# Remote_V2.net
KiCad netlist of a schematic drawn in Altium Designer
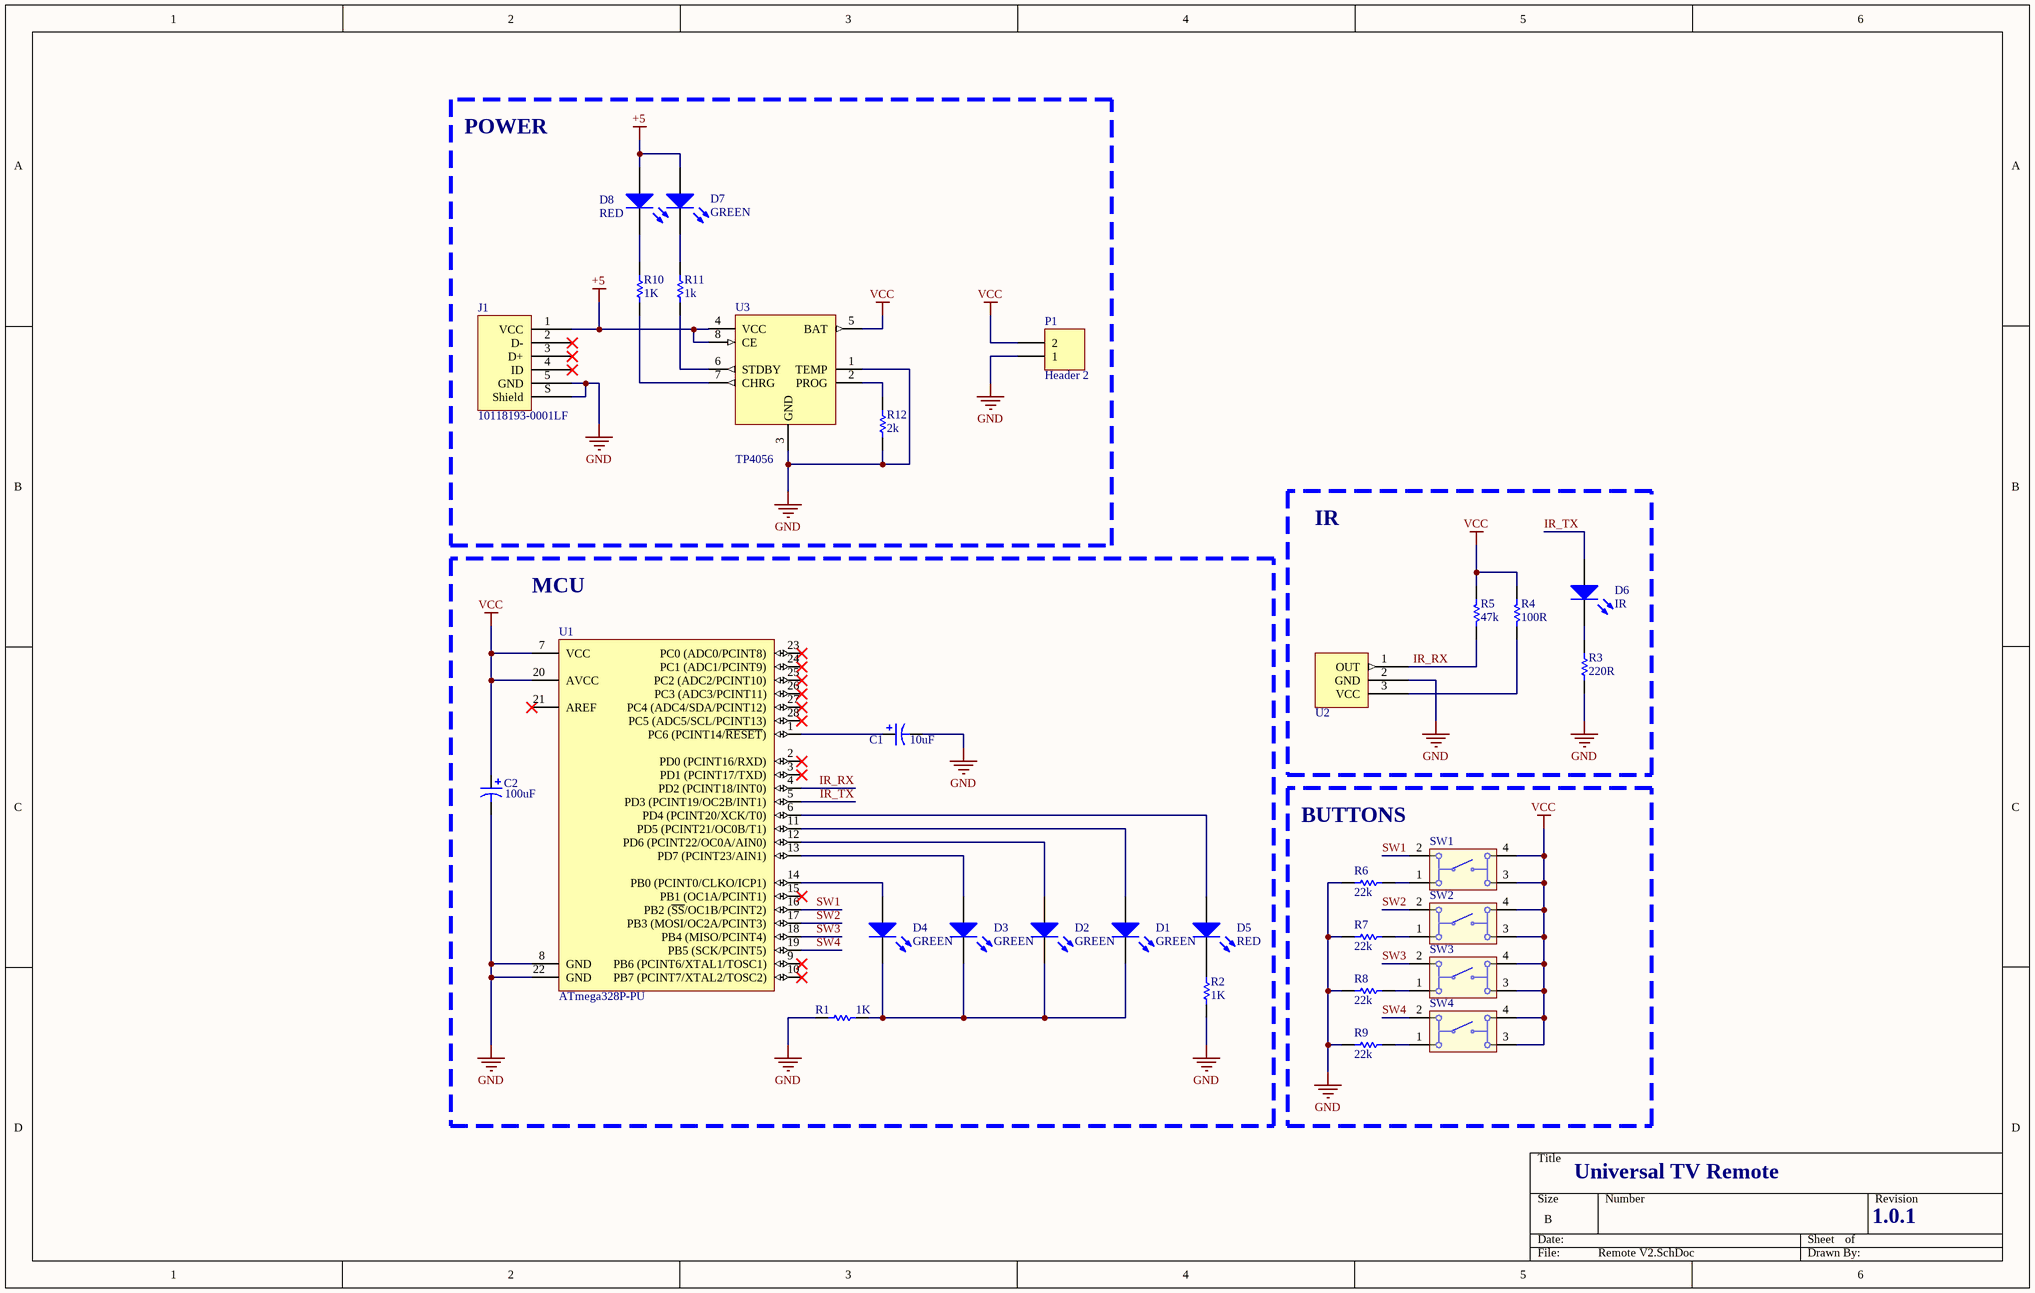
[diagram p0: Remote V2.SchDoc]

(export (version "E")
  (design (tool "Eeschema 10.0.6"))
  (components
    (comp (ref "C1")
      (value "10uF")
      (footprint "5mm CAP")
      (description "Polarized Capacitor (Radial)")
      (fields (field (name "Comment") "Cap Pol1") (field (name "PUBLISHER") "Altium Limited"))
      (libsource (lib "Miscellaneous Devices") (part "Cap Pol1"))
    )
    (comp (ref "C2")
      (value "100uF")
      (footprint "5mm CAP")
      (description "Polarized Capacitor (Radial)")
      (fields (field (name "Comment") "Cap Pol1") (field (name "PUBLISHER") "Altium Limited"))
      (libsource (lib "Miscellaneous Devices") (part "Cap Pol1"))
    )
    (comp (ref "D1")
      (value "GREEN")
      (footprint "5mm CAP")
      (description "Typical INFRARED GaAs LED")
      (fields (field (name "PUBLISHER") "Altium Limited"))
      (libsource (lib "Miscellaneous Devices") (part "LED0"))
    )
    (comp (ref "D2")
      (value "GREEN")
      (footprint "5mm CAP")
      (description "Typical INFRARED GaAs LED")
      (fields (field (name "PUBLISHER") "Altium Limited"))
      (libsource (lib "Miscellaneous Devices") (part "LED0"))
    )
    (comp (ref "D3")
      (value "GREEN")
      (footprint "5mm CAP")
      (description "Typical INFRARED GaAs LED")
      (fields (field (name "PUBLISHER") "Altium Limited"))
      (libsource (lib "Miscellaneous Devices") (part "LED0"))
    )
    (comp (ref "D4")
      (value "GREEN")
      (footprint "5mm CAP")
      (description "Typical INFRARED GaAs LED")
      (fields (field (name "PUBLISHER") "Altium Limited"))
      (libsource (lib "Miscellaneous Devices") (part "LED0"))
    )
    (comp (ref "D5")
      (value "RED")
      (footprint "5mm CAP")
      (description "Typical INFRARED GaAs LED")
      (fields (field (name "PUBLISHER") "Altium Limited"))
      (libsource (lib "Miscellaneous Devices") (part "LED0"))
    )
    (comp (ref "D6")
      (value "IR")
      (footprint "5mm CAP")
      (description "Typical INFRARED GaAs LED")
      (fields (field (name "PUBLISHER") "Altium Limited"))
      (libsource (lib "Miscellaneous Devices") (part "LED0"))
    )
    (comp (ref "D7")
      (value "GREEN")
      (footprint "5mm CAP")
      (description "Typical INFRARED GaAs LED")
      (fields (field (name "PUBLISHER") "Altium Limited"))
      (libsource (lib "Miscellaneous Devices") (part "LED0"))
    )
    (comp (ref "D8")
      (value "RED")
      (footprint "5mm CAP")
      (description "Typical INFRARED GaAs LED")
      (fields (field (name "PUBLISHER") "Altium Limited"))
      (libsource (lib "Miscellaneous Devices") (part "LED0"))
    )
    (comp (ref "J1")
      (value "10118193-0001LF")
      (footprint "FCI USB 10118193-0001LF")
      (description "CONN RCPT USB2.0 MICRO B SMD R/A")
      (fields (field (name "MANUFACTURER") "Amphenol ICC (FCI)"))
      (libsource (lib "Celestial Altium Library - altium_library(1)") (part "USB 2.0 Type B Micro"))
    )
    (comp (ref "P1")
      (value "Header 2")
      (footprint "HDR1X2")
      (description "Header, 2-Pin")
      (fields (field (name "PUBLISHER") "Altium Limited"))
      (libsource (lib "Miscellaneous Connectors") (part "Header 2"))
    )
    (comp (ref "R1")
      (value "1K")
      (footprint "AXIAL-0.3")
      (description "Resistor")
      (fields (field (name "Comment") "Res1") (field (name "PUBLISHER") "Altium Limited"))
      (libsource (lib "Miscellaneous Devices") (part "Res1"))
    )
    (comp (ref "R2")
      (value "1K")
      (footprint "AXIAL-0.3")
      (description "Resistor")
      (fields (field (name "Comment") "Res1") (field (name "PUBLISHER") "Altium Limited"))
      (libsource (lib "Miscellaneous Devices") (part "Res1"))
    )
    (comp (ref "R3")
      (value "220R")
      (footprint "AXIAL-0.3")
      (description "Resistor")
      (fields (field (name "Comment") "Res1") (field (name "PUBLISHER") "Altium Limited"))
      (libsource (lib "Miscellaneous Devices") (part "Res1"))
    )
    (comp (ref "R4")
      (value "100R")
      (footprint "AXIAL-0.3")
      (description "Resistor")
      (fields (field (name "Comment") "Res1") (field (name "PUBLISHER") "Altium Limited"))
      (libsource (lib "Miscellaneous Devices") (part "Res1"))
    )
    (comp (ref "R5")
      (value "47k")
      (footprint "AXIAL-0.3")
      (description "Resistor")
      (fields (field (name "Comment") "Res1") (field (name "PUBLISHER") "Altium Limited"))
      (libsource (lib "Miscellaneous Devices") (part "Res1"))
    )
    (comp (ref "R6")
      (value "22k")
      (footprint "AXIAL-0.3")
      (description "Resistor")
      (fields (field (name "Comment") "Res1") (field (name "PUBLISHER") "Altium Limited"))
      (libsource (lib "Miscellaneous Devices") (part "Res1"))
    )
    (comp (ref "R7")
      (value "22k")
      (footprint "AXIAL-0.3")
      (description "Resistor")
      (fields (field (name "Comment") "Res1") (field (name "PUBLISHER") "Altium Limited"))
      (libsource (lib "Miscellaneous Devices") (part "Res1"))
    )
    (comp (ref "R8")
      (value "22k")
      (footprint "AXIAL-0.3")
      (description "Resistor")
      (fields (field (name "Comment") "Res1") (field (name "PUBLISHER") "Altium Limited"))
      (libsource (lib "Miscellaneous Devices") (part "Res1"))
    )
    (comp (ref "R9")
      (value "22k")
      (footprint "AXIAL-0.3")
      (description "Resistor")
      (fields (field (name "Comment") "Res1") (field (name "PUBLISHER") "Altium Limited"))
      (libsource (lib "Miscellaneous Devices") (part "Res1"))
    )
    (comp (ref "R10")
      (value "1K")
      (footprint "6-0805_N")
      (description "Resistor")
      (fields (field (name "Comment") "Res1") (field (name "PUBLISHER") "Altium Limited"))
      (libsource (lib "Miscellaneous Devices") (part "Res1"))
    )
    (comp (ref "R11")
      (value "1k")
      (footprint "6-0805_N")
      (description "Resistor")
      (fields (field (name "Comment") "Res1") (field (name "PUBLISHER") "Altium Limited"))
      (libsource (lib "Miscellaneous Devices") (part "Res1"))
    )
    (comp (ref "R12")
      (value "2k")
      (footprint "6-0805_N")
      (description "Resistor")
      (fields (field (name "Comment") "Res1") (field (name "PUBLISHER") "Altium Limited"))
      (libsource (lib "Miscellaneous Devices") (part "Res1"))
    )
    (comp (ref "SW1")
      (value "430476085716")
      (footprint "SW_1825910-6-4")
      (description "WS-TATV THT Tact Switch 12X12 mm")
      (libsource (lib "WS-TATV THT Tact Switch 12X12 mm") (part "430476085716"))
    )
    (comp (ref "SW2")
      (value "430476085716")
      (footprint "SW_1825910-6-4")
      (description "WS-TATV THT Tact Switch 12X12 mm")
      (libsource (lib "WS-TATV THT Tact Switch 12X12 mm") (part "430476085716"))
    )
    (comp (ref "SW3")
      (value "430476085716")
      (footprint "SW_1825910-6-4")
      (description "WS-TATV THT Tact Switch 12X12 mm")
      (libsource (lib "WS-TATV THT Tact Switch 12X12 mm") (part "430476085716"))
    )
    (comp (ref "SW4")
      (value "430476085716")
      (footprint "SW_1825910-6-4")
      (description "WS-TATV THT Tact Switch 12X12 mm")
      (libsource (lib "WS-TATV THT Tact Switch 12X12 mm") (part "430476085716"))
    )
    (comp (ref "U1")
      (value "ATmega328P-PU")
      (footprint "28P3")
      (libsource (lib "Atmel Microcontroller megaAVR") (part "ATmega328P-PU"))
    )
    (comp (ref "U2")
      (value "CHO 1838")
      (footprint "TO-220-AB")
      (description "IR Receiver")
      (libsource (lib "Symobls") (part "CHO 1838"))
    )
    (comp (ref "U3") (value "TP4056") (footprint "Universal SOP 8") (libsource (lib "SMD") (part "TP4056")))
  )
  (nets
    (net (code "1") (name "+5") (class "Default")
      (node (ref "D7") (pin "1") (pinfunction "A_1") (pintype "passive"))
      (node (ref "D8") (pin "1") (pinfunction "A_1") (pintype "passive"))
      (node (ref "J1") (pin "1") (pinfunction "VCC_1") (pintype "passive"))
      (node (ref "U3") (pin "4") (pinfunction "VCC_4") (pintype "power_in"))
      (node (ref "U3") (pin "8") (pinfunction "CE_8") (pintype "input"))
    )
    (net (code "2") (name "/IR_RX") (class "Default")
      (node (ref "R5") (pin "1") (pinfunction "1_1") (pintype "passive"))
      (node (ref "U1") (pin "4") (pinfunction "PD2_(PCINT18/INT0)_4") (pintype "bidirectional"))
      (node (ref "U2") (pin "1") (pinfunction "OUT_1") (pintype "output"))
    )
    (net (code "3") (name "/IR_TX") (class "Default")
      (node (ref "D6") (pin "1") (pinfunction "A_1") (pintype "passive"))
      (node (ref "U1") (pin "5") (pinfunction "PD3_(PCINT19/OC2B/INT1)_5") (pintype "bidirectional"))
    )
    (net (code "4") (name "/SW1") (class "Default")
      (node (ref "SW1") (pin "2") (pinfunction "2_2") (pintype "passive"))
      (node (ref "U1") (pin "16") (pinfunction "PB2_(~{SS}/OC1B/PCINT2)_16") (pintype "bidirectional"))
    )
    (net (code "5") (name "/SW2") (class "Default")
      (node (ref "SW2") (pin "2") (pinfunction "2_2") (pintype "passive"))
      (node (ref "U1") (pin "17") (pinfunction "PB3_(MOSI/OC2A/PCINT3)_17") (pintype "bidirectional"))
    )
    (net (code "6") (name "/SW3") (class "Default")
      (node (ref "SW3") (pin "2") (pinfunction "2_2") (pintype "passive"))
      (node (ref "U1") (pin "18") (pinfunction "PB4_(MISO/PCINT4)_18") (pintype "bidirectional"))
    )
    (net (code "7") (name "/SW4") (class "Default")
      (node (ref "SW4") (pin "2") (pinfunction "2_2") (pintype "passive"))
      (node (ref "U1") (pin "19") (pinfunction "PB5_(SCK/PCINT5)_19") (pintype "bidirectional"))
    )
    (net (code "8") (name "GND") (class "Default")
      (node (ref "C1") (pin "2") (pinfunction "2_2") (pintype "passive"))
      (node (ref "C2") (pin "2") (pinfunction "2_2") (pintype "passive"))
      (node (ref "J1") (pin "5") (pinfunction "GND_5") (pintype "passive"))
      (node (ref "J1") (pin "S") (pinfunction "Shield_S") (pintype "passive"))
      (node (ref "P1") (pin "1") (pinfunction "1_1") (pintype "passive"))
      (node (ref "R1") (pin "1") (pinfunction "1_1") (pintype "passive"))
      (node (ref "R12") (pin "1") (pinfunction "1_1") (pintype "passive"))
      (node (ref "R2") (pin "1") (pinfunction "1_1") (pintype "passive"))
      (node (ref "R3") (pin "1") (pinfunction "1_1") (pintype "passive"))
      (node (ref "R6") (pin "1") (pinfunction "1_1") (pintype "passive"))
      (node (ref "R7") (pin "1") (pinfunction "1_1") (pintype "passive"))
      (node (ref "R8") (pin "1") (pinfunction "1_1") (pintype "passive"))
      (node (ref "R9") (pin "1") (pinfunction "1_1") (pintype "passive"))
      (node (ref "U1") (pin "22") (pinfunction "GND_22") (pintype "power_in"))
      (node (ref "U1") (pin "8") (pinfunction "GND_8") (pintype "power_in"))
      (node (ref "U2") (pin "2") (pinfunction "GND_2") (pintype "power_in"))
      (node (ref "U3") (pin "1") (pinfunction "TEMP_1") (pintype "passive"))
      (node (ref "U3") (pin "3") (pinfunction "GND_3") (pintype "power_in"))
    )
    (net (code "9") (name "Net-(D1-A)") (class "Default")
      (node (ref "D1") (pin "1") (pinfunction "A_1") (pintype "passive"))
      (node (ref "U1") (pin "11") (pinfunction "PD5_(PCINT21/OC0B/T1)_11") (pintype "bidirectional"))
    )
    (net (code "10") (name "Net-(D1-K)") (class "Default")
      (node (ref "D1") (pin "2") (pinfunction "K_2") (pintype "passive"))
      (node (ref "D2") (pin "2") (pinfunction "K_2") (pintype "passive"))
      (node (ref "D3") (pin "2") (pinfunction "K_2") (pintype "passive"))
      (node (ref "D4") (pin "2") (pinfunction "K_2") (pintype "passive"))
      (node (ref "R1") (pin "2") (pinfunction "2_2") (pintype "passive"))
    )
    (net (code "11") (name "Net-(D2-A)") (class "Default")
      (node (ref "D2") (pin "1") (pinfunction "A_1") (pintype "passive"))
      (node (ref "U1") (pin "12") (pinfunction "PD6_(PCINT22/OC0A/AIN0)_12") (pintype "bidirectional"))
    )
    (net (code "12") (name "Net-(D3-A)") (class "Default")
      (node (ref "D3") (pin "1") (pinfunction "A_1") (pintype "passive"))
      (node (ref "U1") (pin "13") (pinfunction "PD7_(PCINT23/AIN1)_13") (pintype "bidirectional"))
    )
    (net (code "13") (name "Net-(D4-A)") (class "Default")
      (node (ref "D4") (pin "1") (pinfunction "A_1") (pintype "passive"))
      (node (ref "U1") (pin "14") (pinfunction "PB0_(PCINT0/CLKO/ICP1)_14") (pintype "bidirectional"))
    )
    (net (code "14") (name "Net-(D5-A)") (class "Default")
      (node (ref "D5") (pin "1") (pinfunction "A_1") (pintype "passive"))
      (node (ref "U1") (pin "6") (pinfunction "PD4_(PCINT20/XCK/T0)_6") (pintype "bidirectional"))
    )
    (net (code "15") (name "Net-(D5-K)") (class "Default")
      (node (ref "D5") (pin "2") (pinfunction "K_2") (pintype "passive"))
      (node (ref "R2") (pin "2") (pinfunction "2_2") (pintype "passive"))
    )
    (net (code "16") (name "Net-(D6-K)") (class "Default")
      (node (ref "D6") (pin "2") (pinfunction "K_2") (pintype "passive"))
      (node (ref "R3") (pin "2") (pinfunction "2_2") (pintype "passive"))
    )
    (net (code "17") (name "Net-(D7-K)") (class "Default")
      (node (ref "D7") (pin "2") (pinfunction "K_2") (pintype "passive"))
      (node (ref "R11") (pin "2") (pinfunction "2_2") (pintype "passive"))
    )
    (net (code "18") (name "Net-(D8-K)") (class "Default")
      (node (ref "D8") (pin "2") (pinfunction "K_2") (pintype "passive"))
      (node (ref "R10") (pin "2") (pinfunction "2_2") (pintype "passive"))
    )
    (net (code "19") (name "Net-(R6-Pad2)") (class "Default")
      (node (ref "R6") (pin "2") (pinfunction "2_2") (pintype "passive"))
      (node (ref "SW1") (pin "1") (pinfunction "1_1") (pintype "passive"))
    )
    (net (code "20") (name "Net-(R7-Pad2)") (class "Default")
      (node (ref "R7") (pin "2") (pinfunction "2_2") (pintype "passive"))
      (node (ref "SW2") (pin "1") (pinfunction "1_1") (pintype "passive"))
    )
    (net (code "21") (name "Net-(R8-Pad2)") (class "Default")
      (node (ref "R8") (pin "2") (pinfunction "2_2") (pintype "passive"))
      (node (ref "SW3") (pin "1") (pinfunction "1_1") (pintype "passive"))
    )
    (net (code "22") (name "Net-(R9-Pad2)") (class "Default")
      (node (ref "R9") (pin "2") (pinfunction "2_2") (pintype "passive"))
      (node (ref "SW4") (pin "1") (pinfunction "1_1") (pintype "passive"))
    )
    (net (code "23") (name "Net-(U1-PC6_(PCINT14{slash}~{RESET}))") (class "Default")
      (node (ref "C1") (pin "1") (pinfunction "1_1") (pintype "passive"))
      (node (ref "U1") (pin "1") (pinfunction "PC6_(PCINT14/~{RESET})_1") (pintype "bidirectional"))
    )
    (net (code "24") (name "Net-(U2-VCC)") (class "Default")
      (node (ref "R4") (pin "2") (pinfunction "2_2") (pintype "passive"))
      (node (ref "U2") (pin "3") (pinfunction "VCC_3") (pintype "power_in"))
    )
    (net (code "25") (name "Net-(U3-CHRG)") (class "Default")
      (node (ref "R10") (pin "1") (pinfunction "1_1") (pintype "passive"))
      (node (ref "U3") (pin "7") (pinfunction "CHRG_7") (pintype "output"))
    )
    (net (code "26") (name "Net-(U3-PROG)") (class "Default")
      (node (ref "R12") (pin "2") (pinfunction "2_2") (pintype "passive"))
      (node (ref "U3") (pin "2") (pinfunction "PROG_2") (pintype "passive"))
    )
    (net (code "27") (name "Net-(U3-STDBY)") (class "Default")
      (node (ref "R11") (pin "1") (pinfunction "1_1") (pintype "passive"))
      (node (ref "U3") (pin "6") (pinfunction "STDBY_6") (pintype "output"))
    )
    (net (code "28") (name "VCC") (class "Default")
      (node (ref "C2") (pin "1") (pinfunction "1_1") (pintype "passive"))
      (node (ref "P1") (pin "2") (pinfunction "2_2") (pintype "passive"))
      (node (ref "R4") (pin "1") (pinfunction "1_1") (pintype "passive"))
      (node (ref "R5") (pin "2") (pinfunction "2_2") (pintype "passive"))
      (node (ref "SW1") (pin "3") (pinfunction "3_3") (pintype "passive"))
      (node (ref "SW1") (pin "4") (pinfunction "4_4") (pintype "passive"))
      (node (ref "SW2") (pin "3") (pinfunction "3_3") (pintype "passive"))
      (node (ref "SW2") (pin "4") (pinfunction "4_4") (pintype "passive"))
      (node (ref "SW3") (pin "3") (pinfunction "3_3") (pintype "passive"))
      (node (ref "SW3") (pin "4") (pinfunction "4_4") (pintype "passive"))
      (node (ref "SW4") (pin "3") (pinfunction "3_3") (pintype "passive"))
      (node (ref "SW4") (pin "4") (pinfunction "4_4") (pintype "passive"))
      (node (ref "U1") (pin "20") (pinfunction "AVCC_20") (pintype "power_in"))
      (node (ref "U1") (pin "7") (pinfunction "VCC_7") (pintype "power_in"))
      (node (ref "U3") (pin "5") (pinfunction "BAT_5") (pintype "output"))
    )
    (net (code "29") (name "unconnected-(J1-D+-Pad3)") (class "Default")
      (node (ref "J1") (pin "3") (pinfunction "D+_3") (pintype "passive+no_connect"))
    )
    (net (code "30") (name "unconnected-(J1-D--Pad2)") (class "Default")
      (node (ref "J1") (pin "2") (pinfunction "D-_2") (pintype "passive+no_connect"))
    )
    (net (code "31") (name "unconnected-(J1-ID-Pad4)") (class "Default")
      (node (ref "J1") (pin "4") (pinfunction "ID_4") (pintype "passive+no_connect"))
    )
    (net (code "32") (name "unconnected-(U1-AREF-Pad21)") (class "Default")
      (node (ref "U1") (pin "21") (pinfunction "AREF_21") (pintype "power_in+no_connect"))
    )
    (net (code "33") (name "unconnected-(U1-PB1_(OC1A{slash}PCINT1)-Pad15)") (class "Default")
      (node (ref "U1") (pin "15") (pinfunction "PB1_(OC1A/PCINT1)_15") (pintype "bidirectional+no_connect"))
    )
    (net (code "34") (name "unconnected-(U1-PB6_(PCINT6{slash}XTAL1{slash}TOSC1)-Pad9)") (class "Default")
      (node (ref "U1") (pin "9") (pinfunction "PB6_(PCINT6/XTAL1/TOSC1)_9") (pintype "bidirectional+no_connect"))
    )
    (net (code "35") (name "unconnected-(U1-PB7_(PCINT7{slash}XTAL2{slash}TOSC2)-Pad10)") (class "Default")
      (node (ref "U1") (pin "10") (pinfunction "PB7_(PCINT7/XTAL2/TOSC2)_10") (pintype "bidirectional+no_connect"))
    )
    (net (code "36") (name "unconnected-(U1-PC0_(ADC0{slash}PCINT8)-Pad23)") (class "Default")
      (node (ref "U1") (pin "23") (pinfunction "PC0_(ADC0/PCINT8)_23") (pintype "bidirectional+no_connect"))
    )
    (net (code "37") (name "unconnected-(U1-PC1_(ADC1{slash}PCINT9)-Pad24)") (class "Default")
      (node (ref "U1") (pin "24") (pinfunction "PC1_(ADC1/PCINT9)_24") (pintype "bidirectional+no_connect"))
    )
    (net (code "38") (name "unconnected-(U1-PC2_(ADC2{slash}PCINT10)-Pad25)") (class "Default")
      (node (ref "U1") (pin "25") (pinfunction "PC2_(ADC2/PCINT10)_25") (pintype "bidirectional+no_connect"))
    )
    (net (code "39") (name "unconnected-(U1-PC3_(ADC3{slash}PCINT11)-Pad26)") (class "Default")
      (node (ref "U1") (pin "26") (pinfunction "PC3_(ADC3/PCINT11)_26") (pintype "bidirectional+no_connect"))
    )
    (net (code "40") (name "unconnected-(U1-PC4_(ADC4{slash}SDA{slash}PCINT12)-Pad27)") (class "Default")
      (node (ref "U1") (pin "27") (pinfunction "PC4_(ADC4/SDA/PCINT12)_27") (pintype "bidirectional+no_connect"))
    )
    (net (code "41") (name "unconnected-(U1-PC5_(ADC5{slash}SCL{slash}PCINT13)-Pad28)") (class "Default")
      (node (ref "U1") (pin "28") (pinfunction "PC5_(ADC5/SCL/PCINT13)_28") (pintype "bidirectional+no_connect"))
    )
    (net (code "42") (name "unconnected-(U1-PD0_(PCINT16{slash}RXD)-Pad2)") (class "Default")
      (node (ref "U1") (pin "2") (pinfunction "PD0_(PCINT16/RXD)_2") (pintype "bidirectional+no_connect"))
    )
    (net (code "43") (name "unconnected-(U1-PD1_(PCINT17{slash}TXD)-Pad3)") (class "Default")
      (node (ref "U1") (pin "3") (pinfunction "PD1_(PCINT17/TXD)_3") (pintype "bidirectional+no_connect"))
    )
  )
)
